# plotter.net
KiCad netlist of a schematic drawn in EAGLE
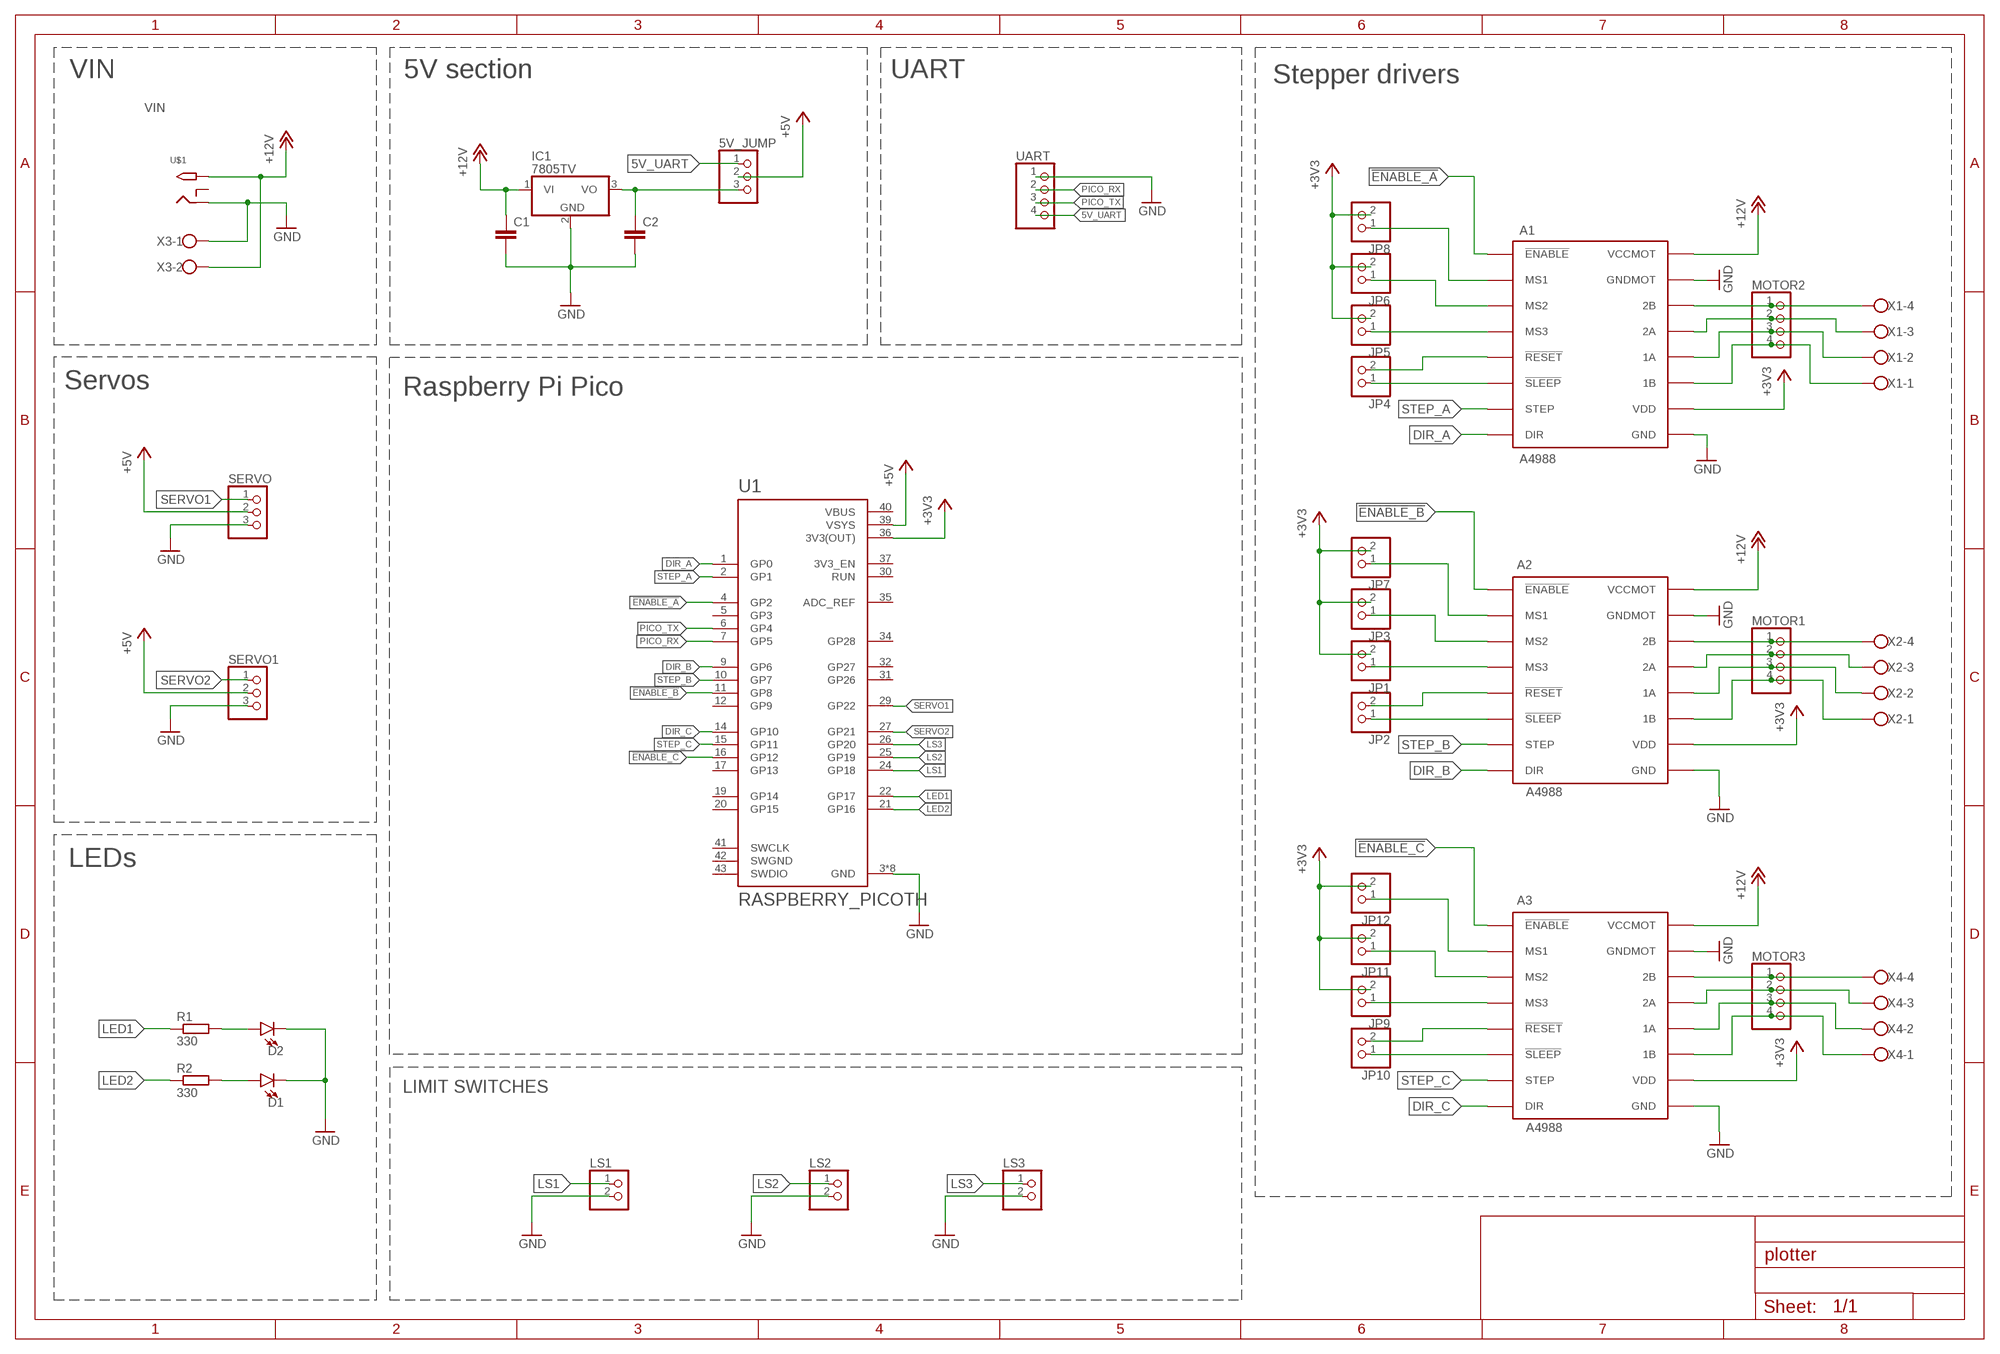
[diagram p0: schematic, sheet 1]

(export (version "E")
  (design (tool "Eeschema 10.0.6"))
  (components
    (comp (ref "5V_JUMP")
      (value "PINHD-1X3")
      (footprint "eagle-import:1X03")
      (libsource (lib "eagle-import") (part "PINHD-1X3"))
    )
    (comp (ref "A1")
      (value "A4988")
      (footprint "eagle-import:A4988")
      (libsource (lib "eagle-import") (part "A4988"))
    )
    (comp (ref "A2")
      (value "A4988")
      (footprint "eagle-import:A4988")
      (libsource (lib "eagle-import") (part "A4988"))
    )
    (comp (ref "A3")
      (value "A4988")
      (footprint "eagle-import:A4988")
      (libsource (lib "eagle-import") (part "A4988"))
    )
    (comp (ref "C1")
      (value "C-EUC0805")
      (footprint "eagle-import:C0805")
      (libsource (lib "eagle-import") (part "C-EUC0805"))
    )
    (comp (ref "C2")
      (value "C-EUC0805")
      (footprint "eagle-import:C0805")
      (libsource (lib "eagle-import") (part "C-EUC0805"))
    )
    (comp (ref "D1")
      (value "LED5MM")
      (footprint "eagle-import:LED_5MM")
      (libsource (lib "eagle-import") (part "LED5MM"))
    )
    (comp (ref "D2")
      (value "LED5MM")
      (footprint "eagle-import:LED_5MM")
      (libsource (lib "eagle-import") (part "LED5MM"))
    )
    (comp (ref "IC1")
      (value "7805TV")
      (footprint "eagle-import:TO220V")
      (libsource (lib "eagle-import") (part "78TV05"))
    )
    (comp (ref "JP1")
      (value "PINHD-1X2")
      (footprint "eagle-import:1X02")
      (libsource (lib "eagle-import") (part "PINHD-1X2"))
    )
    (comp (ref "JP2")
      (value "PINHD-1X2")
      (footprint "eagle-import:1X02")
      (libsource (lib "eagle-import") (part "PINHD-1X2"))
    )
    (comp (ref "JP3")
      (value "PINHD-1X2")
      (footprint "eagle-import:1X02")
      (libsource (lib "eagle-import") (part "PINHD-1X2"))
    )
    (comp (ref "JP4")
      (value "PINHD-1X2")
      (footprint "eagle-import:1X02")
      (libsource (lib "eagle-import") (part "PINHD-1X2"))
    )
    (comp (ref "JP5")
      (value "PINHD-1X2")
      (footprint "eagle-import:1X02")
      (libsource (lib "eagle-import") (part "PINHD-1X2"))
    )
    (comp (ref "JP6")
      (value "PINHD-1X2")
      (footprint "eagle-import:1X02")
      (libsource (lib "eagle-import") (part "PINHD-1X2"))
    )
    (comp (ref "JP7")
      (value "PINHD-1X2")
      (footprint "eagle-import:1X02")
      (libsource (lib "eagle-import") (part "PINHD-1X2"))
    )
    (comp (ref "JP8")
      (value "PINHD-1X2")
      (footprint "eagle-import:1X02")
      (libsource (lib "eagle-import") (part "PINHD-1X2"))
    )
    (comp (ref "JP9")
      (value "PINHD-1X2")
      (footprint "eagle-import:1X02")
      (libsource (lib "eagle-import") (part "PINHD-1X2"))
    )
    (comp (ref "JP10")
      (value "PINHD-1X2")
      (footprint "eagle-import:1X02")
      (libsource (lib "eagle-import") (part "PINHD-1X2"))
    )
    (comp (ref "JP11")
      (value "PINHD-1X2")
      (footprint "eagle-import:1X02")
      (libsource (lib "eagle-import") (part "PINHD-1X2"))
    )
    (comp (ref "JP12")
      (value "PINHD-1X2")
      (footprint "eagle-import:1X02")
      (libsource (lib "eagle-import") (part "PINHD-1X2"))
    )
    (comp (ref "LS1")
      (value "PINHD-1X2")
      (footprint "eagle-import:1X02")
      (libsource (lib "eagle-import") (part "PINHD-1X2"))
    )
    (comp (ref "LS2")
      (value "PINHD-1X2")
      (footprint "eagle-import:1X02")
      (libsource (lib "eagle-import") (part "PINHD-1X2"))
    )
    (comp (ref "LS3")
      (value "PINHD-1X2")
      (footprint "eagle-import:1X02")
      (libsource (lib "eagle-import") (part "PINHD-1X2"))
    )
    (comp (ref "MOTOR1")
      (value "PINHD-1X4")
      (footprint "eagle-import:1X04")
      (libsource (lib "eagle-import") (part "PINHD-1X4"))
    )
    (comp (ref "MOTOR2")
      (value "PINHD-1X4")
      (footprint "eagle-import:1X04")
      (libsource (lib "eagle-import") (part "PINHD-1X4"))
    )
    (comp (ref "MOTOR3")
      (value "PINHD-1X4")
      (footprint "eagle-import:1X04")
      (libsource (lib "eagle-import") (part "PINHD-1X4"))
    )
    (comp (ref "R1")
      (value "330")
      (footprint "eagle-import:R0805")
      (libsource (lib "eagle-import") (part "R-EU_R0805"))
    )
    (comp (ref "R2")
      (value "330")
      (footprint "eagle-import:R0805")
      (libsource (lib "eagle-import") (part "R-EU_R0805"))
    )
    (comp (ref "SERVO")
      (value "PINHD-1X3")
      (footprint "eagle-import:1X03")
      (libsource (lib "eagle-import") (part "PINHD-1X3"))
    )
    (comp (ref "SERVO1")
      (value "PINHD-1X3")
      (footprint "eagle-import:1X03")
      (libsource (lib "eagle-import") (part "PINHD-1X3"))
    )
    (comp (ref "U$1")
      (value "2.1MMJACKTHM")
      (footprint "eagle-import:PJ-102A")
      (libsource (lib "eagle-import") (part "2.1MMJACKTHM"))
    )
    (comp (ref "U1")
      (value "RASPBERRY_PICOTH")
      (footprint "eagle-import:PICO-PKG-TH")
      (libsource (lib "eagle-import") (part "RASPBERRY_PICOTH"))
    )
    (comp (ref "UART")
      (value "PINHD-1X4")
      (footprint "eagle-import:1X04")
      (libsource (lib "eagle-import") (part "PINHD-1X4"))
    )
    (comp (ref "X1")
      (value "W237-4")
      (footprint "eagle-import:W237-4")
      (libsource (lib "eagle-import") (part "W237-4"))
    )
    (comp (ref "X2")
      (value "W237-4")
      (footprint "eagle-import:W237-4")
      (libsource (lib "eagle-import") (part "W237-4"))
    )
    (comp (ref "X3")
      (value "W237-102")
      (footprint "eagle-import:W237-102")
      (fields (field (name "MPN") "237-102"))
      (libsource (lib "eagle-import") (part "W237-102"))
    )
    (comp (ref "X4")
      (value "W237-4")
      (footprint "eagle-import:W237-4")
      (libsource (lib "eagle-import") (part "W237-4"))
    )
  )
  (nets
    (net (code "1") (name "+3V3") (class "Default")
      (node (ref "A1") (pin "VDD") (pinfunction "VDD_VDD") (pintype "bidirectional"))
      (node (ref "A2") (pin "VDD") (pinfunction "VDD_VDD") (pintype "bidirectional"))
      (node (ref "A3") (pin "VDD") (pinfunction "VDD_VDD") (pintype "bidirectional"))
      (node (ref "JP1") (pin "2") (pinfunction "2_2") (pintype "passive"))
      (node (ref "JP11") (pin "2") (pinfunction "2_2") (pintype "passive"))
      (node (ref "JP12") (pin "2") (pinfunction "2_2") (pintype "passive"))
      (node (ref "JP3") (pin "2") (pinfunction "2_2") (pintype "passive"))
      (node (ref "JP5") (pin "2") (pinfunction "2_2") (pintype "passive"))
      (node (ref "JP6") (pin "2") (pinfunction "2_2") (pintype "passive"))
      (node (ref "JP7") (pin "2") (pinfunction "2_2") (pintype "passive"))
      (node (ref "JP8") (pin "2") (pinfunction "2_2") (pintype "passive"))
      (node (ref "JP9") (pin "2") (pinfunction "2_2") (pintype "passive"))
      (node (ref "U1") (pin "36") (pinfunction "3V3(OUT)_36") (pintype "power_in"))
    )
    (net (code "2") (name "+5V") (class "Default")
      (node (ref "5V_JUMP") (pin "2") (pinfunction "2_2") (pintype "passive"))
      (node (ref "SERVO") (pin "2") (pinfunction "2_2") (pintype "passive"))
      (node (ref "SERVO1") (pin "2") (pinfunction "2_2") (pintype "passive"))
      (node (ref "U1") (pin "39") (pinfunction "VSYS_39") (pintype "power_in"))
    )
    (net (code "3") (name "+12V") (class "Default")
      (node (ref "A1") (pin "VCCMOT") (pinfunction "VCCMOT_VCCMOT") (pintype "bidirectional"))
      (node (ref "A2") (pin "VCCMOT") (pinfunction "VCCMOT_VCCMOT") (pintype "bidirectional"))
      (node (ref "A3") (pin "VCCMOT") (pinfunction "VCCMOT_VCCMOT") (pintype "bidirectional"))
      (node (ref "C1") (pin "1") (pinfunction "1_1") (pintype "passive"))
      (node (ref "IC1") (pin "1") (pinfunction "VI_1") (pintype "input"))
      (node (ref "U$1") (pin "TIP") (pinfunction "TIP_TIP") (pintype "bidirectional"))
      (node (ref "X3") (pin "2") (pinfunction "KL_2") (pintype "passive"))
    )
    (net (code "4") (name "/SWGND") (class "Default")
      (node (ref "U1") (pin "42") (pinfunction "SWGND_42") (pintype "power_in"))
    )
    (net (code "5") (name "/VBUS") (class "Default")
      (node (ref "U1") (pin "40") (pinfunction "VBUS_40") (pintype "power_in"))
    )
    (net (code "6") (name "/~{ENABLE_A}") (class "Default")
      (node (ref "A1") (pin "!ENABLE") (pinfunction "~{ENABLE}_!ENABLE") (pintype "bidirectional"))
      (node (ref "U1") (pin "4") (pinfunction "GP2_4") (pintype "bidirectional"))
    )
    (net (code "7") (name "/~{ENABLE_B}") (class "Default")
      (node (ref "A2") (pin "!ENABLE") (pinfunction "~{ENABLE}_!ENABLE") (pintype "bidirectional"))
      (node (ref "U1") (pin "11") (pinfunction "GP8_11") (pintype "bidirectional"))
    )
    (net (code "8") (name "/~{ENABLE_C}") (class "Default")
      (node (ref "A3") (pin "!ENABLE") (pinfunction "~{ENABLE}_!ENABLE") (pintype "bidirectional"))
      (node (ref "U1") (pin "16") (pinfunction "GP12_16") (pintype "bidirectional"))
    )
    (net (code "9") (name "5V_UART") (class "Default")
      (node (ref "5V_JUMP") (pin "1") (pinfunction "1_1") (pintype "passive"))
      (node (ref "UART") (pin "4") (pinfunction "4_4") (pintype "passive"))
    )
    (net (code "10") (name "DIR_A") (class "Default")
      (node (ref "A1") (pin "DIR") (pinfunction "DIR_DIR") (pintype "bidirectional"))
      (node (ref "U1") (pin "1") (pinfunction "GP0_1") (pintype "bidirectional"))
    )
    (net (code "11") (name "DIR_B") (class "Default")
      (node (ref "A2") (pin "DIR") (pinfunction "DIR_DIR") (pintype "bidirectional"))
      (node (ref "U1") (pin "9") (pinfunction "GP6_9") (pintype "bidirectional"))
    )
    (net (code "12") (name "DIR_C") (class "Default")
      (node (ref "A3") (pin "DIR") (pinfunction "DIR_DIR") (pintype "bidirectional"))
      (node (ref "U1") (pin "14") (pinfunction "GP10_14") (pintype "bidirectional"))
    )
    (net (code "13") (name "GND") (class "Default")
      (node (ref "A1") (pin "GND") (pinfunction "GND_GND") (pintype "bidirectional"))
      (node (ref "A1") (pin "GNDMOT") (pinfunction "GNDMOT_GNDMOT") (pintype "bidirectional"))
      (node (ref "A2") (pin "GND") (pinfunction "GND_GND") (pintype "bidirectional"))
      (node (ref "A2") (pin "GNDMOT") (pinfunction "GNDMOT_GNDMOT") (pintype "bidirectional"))
      (node (ref "A3") (pin "GND") (pinfunction "GND_GND") (pintype "bidirectional"))
      (node (ref "A3") (pin "GNDMOT") (pinfunction "GNDMOT_GNDMOT") (pintype "bidirectional"))
      (node (ref "C1") (pin "2") (pinfunction "2_2") (pintype "passive"))
      (node (ref "C2") (pin "2") (pinfunction "2_2") (pintype "passive"))
      (node (ref "D1") (pin "K") (pinfunction "C_K") (pintype "passive"))
      (node (ref "D2") (pin "K") (pinfunction "C_K") (pintype "passive"))
      (node (ref "IC1") (pin "2") (pinfunction "GND_2") (pintype "passive"))
      (node (ref "LS1") (pin "2") (pinfunction "2_2") (pintype "passive"))
      (node (ref "LS2") (pin "2") (pinfunction "2_2") (pintype "passive"))
      (node (ref "LS3") (pin "2") (pinfunction "2_2") (pintype "passive"))
      (node (ref "SERVO") (pin "3") (pinfunction "3_3") (pintype "passive"))
      (node (ref "SERVO1") (pin "3") (pinfunction "3_3") (pintype "passive"))
      (node (ref "U$1") (pin "RING") (pinfunction "RING_RING") (pintype "bidirectional"))
      (node (ref "U1") (pin "13") (pinfunction "GND_13") (pintype "power_in"))
      (node (ref "U1") (pin "18") (pinfunction "GND_18") (pintype "power_in"))
      (node (ref "U1") (pin "23") (pinfunction "GND_23") (pintype "power_in"))
      (node (ref "U1") (pin "28") (pinfunction "GND_28") (pintype "power_in"))
      (node (ref "U1") (pin "3") (pinfunction "GND_3") (pintype "power_in"))
      (node (ref "U1") (pin "33") (pinfunction "GND_33") (pintype "power_in"))
      (node (ref "U1") (pin "38") (pinfunction "GND_38") (pintype "power_in"))
      (node (ref "U1") (pin "8") (pinfunction "GND_8") (pintype "power_in"))
      (node (ref "UART") (pin "1") (pinfunction "1_1") (pintype "passive"))
      (node (ref "X3") (pin "1") (pinfunction "KL_1") (pintype "passive"))
    )
    (net (code "14") (name "LED1") (class "Default")
      (node (ref "R1") (pin "1") (pinfunction "1_1") (pintype "passive"))
      (node (ref "U1") (pin "22") (pinfunction "GP17_22") (pintype "bidirectional"))
    )
    (net (code "15") (name "LED2") (class "Default")
      (node (ref "R2") (pin "1") (pinfunction "1_1") (pintype "passive"))
      (node (ref "U1") (pin "21") (pinfunction "GP16_21") (pintype "bidirectional"))
    )
    (net (code "16") (name "LS1") (class "Default")
      (node (ref "LS1") (pin "1") (pinfunction "1_1") (pintype "passive"))
      (node (ref "U1") (pin "24") (pinfunction "GP18_24") (pintype "bidirectional"))
    )
    (net (code "17") (name "LS2") (class "Default")
      (node (ref "LS2") (pin "1") (pinfunction "1_1") (pintype "passive"))
      (node (ref "U1") (pin "25") (pinfunction "GP19_25") (pintype "bidirectional"))
    )
    (net (code "18") (name "LS3") (class "Default")
      (node (ref "LS3") (pin "1") (pinfunction "1_1") (pintype "passive"))
      (node (ref "U1") (pin "26") (pinfunction "GP20_26") (pintype "bidirectional"))
    )
    (net (code "19") (name "Net-(A1-PadMS1)") (class "Default")
      (node (ref "A1") (pin "MS1") (pinfunction "MS1_MS1") (pintype "bidirectional"))
      (node (ref "JP8") (pin "1") (pinfunction "1_1") (pintype "passive"))
    )
    (net (code "20") (name "Net-(A1-PadMS2)") (class "Default")
      (node (ref "A1") (pin "MS2") (pinfunction "MS2_MS2") (pintype "bidirectional"))
      (node (ref "JP6") (pin "1") (pinfunction "1_1") (pintype "passive"))
    )
    (net (code "21") (name "Net-(A1-PadMS3)") (class "Default")
      (node (ref "A1") (pin "MS3") (pinfunction "MS3_MS3") (pintype "bidirectional"))
      (node (ref "JP5") (pin "1") (pinfunction "1_1") (pintype "passive"))
    )
    (net (code "22") (name "Net-(A1-~{RESET})") (class "Default")
      (node (ref "A1") (pin "!RESET") (pinfunction "~{RESET}_!RESET") (pintype "bidirectional"))
      (node (ref "JP4") (pin "2") (pinfunction "2_2") (pintype "passive"))
    )
    (net (code "23") (name "Net-(A1-~{SLEEP})") (class "Default")
      (node (ref "A1") (pin "!SLEEP") (pinfunction "~{SLEEP}_!SLEEP") (pintype "bidirectional"))
      (node (ref "JP4") (pin "1") (pinfunction "1_1") (pintype "passive"))
    )
    (net (code "24") (name "Net-(A2-PadMS1)") (class "Default")
      (node (ref "A2") (pin "MS1") (pinfunction "MS1_MS1") (pintype "bidirectional"))
      (node (ref "JP7") (pin "1") (pinfunction "1_1") (pintype "passive"))
    )
    (net (code "25") (name "Net-(A2-PadMS2)") (class "Default")
      (node (ref "A2") (pin "MS2") (pinfunction "MS2_MS2") (pintype "bidirectional"))
      (node (ref "JP3") (pin "1") (pinfunction "1_1") (pintype "passive"))
    )
    (net (code "26") (name "Net-(A2-PadMS3)") (class "Default")
      (node (ref "A2") (pin "MS3") (pinfunction "MS3_MS3") (pintype "bidirectional"))
      (node (ref "JP1") (pin "1") (pinfunction "1_1") (pintype "passive"))
    )
    (net (code "27") (name "Net-(A2-~{RESET})") (class "Default")
      (node (ref "A2") (pin "!RESET") (pinfunction "~{RESET}_!RESET") (pintype "bidirectional"))
      (node (ref "JP2") (pin "2") (pinfunction "2_2") (pintype "passive"))
    )
    (net (code "28") (name "Net-(A2-~{SLEEP})") (class "Default")
      (node (ref "A2") (pin "!SLEEP") (pinfunction "~{SLEEP}_!SLEEP") (pintype "bidirectional"))
      (node (ref "JP2") (pin "1") (pinfunction "1_1") (pintype "passive"))
    )
    (net (code "29") (name "Net-(A3-PadMS1)") (class "Default")
      (node (ref "A3") (pin "MS1") (pinfunction "MS1_MS1") (pintype "bidirectional"))
      (node (ref "JP12") (pin "1") (pinfunction "1_1") (pintype "passive"))
    )
    (net (code "30") (name "Net-(A3-PadMS2)") (class "Default")
      (node (ref "A3") (pin "MS2") (pinfunction "MS2_MS2") (pintype "bidirectional"))
      (node (ref "JP11") (pin "1") (pinfunction "1_1") (pintype "passive"))
    )
    (net (code "31") (name "Net-(A3-PadMS3)") (class "Default")
      (node (ref "A3") (pin "MS3") (pinfunction "MS3_MS3") (pintype "bidirectional"))
      (node (ref "JP9") (pin "1") (pinfunction "1_1") (pintype "passive"))
    )
    (net (code "32") (name "Net-(A3-~{RESET})") (class "Default")
      (node (ref "A3") (pin "!RESET") (pinfunction "~{RESET}_!RESET") (pintype "bidirectional"))
      (node (ref "JP10") (pin "2") (pinfunction "2_2") (pintype "passive"))
    )
    (net (code "33") (name "Net-(A3-~{SLEEP})") (class "Default")
      (node (ref "A3") (pin "!SLEEP") (pinfunction "~{SLEEP}_!SLEEP") (pintype "bidirectional"))
      (node (ref "JP10") (pin "1") (pinfunction "1_1") (pintype "passive"))
    )
    (net (code "34") (name "Net-(D1-PadA)") (class "Default")
      (node (ref "D1") (pin "A") (pinfunction "A_A") (pintype "passive"))
      (node (ref "R2") (pin "2") (pinfunction "2_2") (pintype "passive"))
    )
    (net (code "35") (name "Net-(D2-PadA)") (class "Default")
      (node (ref "D2") (pin "A") (pinfunction "A_A") (pintype "passive"))
      (node (ref "R1") (pin "2") (pinfunction "2_2") (pintype "passive"))
    )
    (net (code "36") (name "Net-(IC1-VO)") (class "Default")
      (node (ref "5V_JUMP") (pin "3") (pinfunction "3_3") (pintype "passive"))
      (node (ref "C2") (pin "1") (pinfunction "1_1") (pintype "passive"))
      (node (ref "IC1") (pin "3") (pinfunction "VO_3") (pintype "passive"))
    )
    (net (code "37") (name "Net-(X1A-KL)") (class "Default")
      (node (ref "A1") (pin "1B") (pinfunction "1B_1B") (pintype "bidirectional"))
      (node (ref "MOTOR2") (pin "4") (pinfunction "4_4") (pintype "passive"))
      (node (ref "X1") (pin "1") (pinfunction "KL_1") (pintype "passive"))
    )
    (net (code "38") (name "Net-(X1B-KL)") (class "Default")
      (node (ref "A1") (pin "1A") (pinfunction "1A_1A") (pintype "bidirectional"))
      (node (ref "MOTOR2") (pin "3") (pinfunction "3_3") (pintype "passive"))
      (node (ref "X1") (pin "2") (pinfunction "KL_2") (pintype "passive"))
    )
    (net (code "39") (name "Net-(X1C-KL)") (class "Default")
      (node (ref "A1") (pin "2A") (pinfunction "2A_2A") (pintype "bidirectional"))
      (node (ref "MOTOR2") (pin "2") (pinfunction "2_2") (pintype "passive"))
      (node (ref "X1") (pin "3") (pinfunction "KL_3") (pintype "passive"))
    )
    (net (code "40") (name "Net-(X1D-KL)") (class "Default")
      (node (ref "A1") (pin "2B") (pinfunction "2B_2B") (pintype "bidirectional"))
      (node (ref "MOTOR2") (pin "1") (pinfunction "1_1") (pintype "passive"))
      (node (ref "X1") (pin "4") (pinfunction "KL_4") (pintype "passive"))
    )
    (net (code "41") (name "Net-(X2A-KL)") (class "Default")
      (node (ref "A2") (pin "1B") (pinfunction "1B_1B") (pintype "bidirectional"))
      (node (ref "MOTOR1") (pin "4") (pinfunction "4_4") (pintype "passive"))
      (node (ref "X2") (pin "1") (pinfunction "KL_1") (pintype "passive"))
    )
    (net (code "42") (name "Net-(X2B-KL)") (class "Default")
      (node (ref "A2") (pin "1A") (pinfunction "1A_1A") (pintype "bidirectional"))
      (node (ref "MOTOR1") (pin "3") (pinfunction "3_3") (pintype "passive"))
      (node (ref "X2") (pin "2") (pinfunction "KL_2") (pintype "passive"))
    )
    (net (code "43") (name "Net-(X2C-KL)") (class "Default")
      (node (ref "A2") (pin "2A") (pinfunction "2A_2A") (pintype "bidirectional"))
      (node (ref "MOTOR1") (pin "2") (pinfunction "2_2") (pintype "passive"))
      (node (ref "X2") (pin "3") (pinfunction "KL_3") (pintype "passive"))
    )
    (net (code "44") (name "Net-(X2D-KL)") (class "Default")
      (node (ref "A2") (pin "2B") (pinfunction "2B_2B") (pintype "bidirectional"))
      (node (ref "MOTOR1") (pin "1") (pinfunction "1_1") (pintype "passive"))
      (node (ref "X2") (pin "4") (pinfunction "KL_4") (pintype "passive"))
    )
    (net (code "45") (name "Net-(X4A-KL)") (class "Default")
      (node (ref "A3") (pin "1B") (pinfunction "1B_1B") (pintype "bidirectional"))
      (node (ref "MOTOR3") (pin "4") (pinfunction "4_4") (pintype "passive"))
      (node (ref "X4") (pin "1") (pinfunction "KL_1") (pintype "passive"))
    )
    (net (code "46") (name "Net-(X4B-KL)") (class "Default")
      (node (ref "A3") (pin "1A") (pinfunction "1A_1A") (pintype "bidirectional"))
      (node (ref "MOTOR3") (pin "3") (pinfunction "3_3") (pintype "passive"))
      (node (ref "X4") (pin "2") (pinfunction "KL_2") (pintype "passive"))
    )
    (net (code "47") (name "Net-(X4C-KL)") (class "Default")
      (node (ref "A3") (pin "2A") (pinfunction "2A_2A") (pintype "bidirectional"))
      (node (ref "MOTOR3") (pin "2") (pinfunction "2_2") (pintype "passive"))
      (node (ref "X4") (pin "3") (pinfunction "KL_3") (pintype "passive"))
    )
    (net (code "48") (name "Net-(X4D-KL)") (class "Default")
      (node (ref "A3") (pin "2B") (pinfunction "2B_2B") (pintype "bidirectional"))
      (node (ref "MOTOR3") (pin "1") (pinfunction "1_1") (pintype "passive"))
      (node (ref "X4") (pin "4") (pinfunction "KL_4") (pintype "passive"))
    )
    (net (code "49") (name "PICO_RX") (class "Default")
      (node (ref "U1") (pin "7") (pinfunction "GP5_7") (pintype "bidirectional"))
      (node (ref "UART") (pin "2") (pinfunction "2_2") (pintype "passive"))
    )
    (net (code "50") (name "PICO_TX") (class "Default")
      (node (ref "U1") (pin "6") (pinfunction "GP4_6") (pintype "bidirectional"))
      (node (ref "UART") (pin "3") (pinfunction "3_3") (pintype "passive"))
    )
    (net (code "51") (name "SERVO1") (class "Default")
      (node (ref "SERVO") (pin "1") (pinfunction "1_1") (pintype "passive"))
      (node (ref "U1") (pin "29") (pinfunction "GP22_29") (pintype "bidirectional"))
    )
    (net (code "52") (name "SERVO2") (class "Default")
      (node (ref "SERVO1") (pin "1") (pinfunction "1_1") (pintype "passive"))
      (node (ref "U1") (pin "27") (pinfunction "GP21_27") (pintype "bidirectional"))
    )
    (net (code "53") (name "STEP_A") (class "Default")
      (node (ref "A1") (pin "STEP") (pinfunction "STEP_STEP") (pintype "bidirectional"))
      (node (ref "U1") (pin "2") (pinfunction "GP1_2") (pintype "bidirectional"))
    )
    (net (code "54") (name "STEP_B") (class "Default")
      (node (ref "A2") (pin "STEP") (pinfunction "STEP_STEP") (pintype "bidirectional"))
      (node (ref "U1") (pin "10") (pinfunction "GP7_10") (pintype "bidirectional"))
    )
    (net (code "55") (name "STEP_C") (class "Default")
      (node (ref "A3") (pin "STEP") (pinfunction "STEP_STEP") (pintype "bidirectional"))
      (node (ref "U1") (pin "15") (pinfunction "GP11_15") (pintype "bidirectional"))
    )
    (net (code "56") (name "unconnected-(U$1-PadRING_SW)") (class "Default")
      (node (ref "U$1") (pin "RING_SW") (pinfunction "RING_SW_RING_SW") (pintype "bidirectional"))
    )
    (net (code "57") (name "unconnected-(U1-3V3_EN-Pad37)") (class "Default")
      (node (ref "U1") (pin "37") (pinfunction "3V3_EN_37") (pintype "input"))
    )
    (net (code "58") (name "unconnected-(U1-ADC_REF-Pad35)") (class "Default")
      (node (ref "U1") (pin "35") (pinfunction "ADC_REF_35") (pintype "input"))
    )
    (net (code "59") (name "unconnected-(U1-GP3-Pad5)") (class "Default")
      (node (ref "U1") (pin "5") (pinfunction "GP3_5") (pintype "bidirectional"))
    )
    (net (code "60") (name "unconnected-(U1-GP9-Pad12)") (class "Default")
      (node (ref "U1") (pin "12") (pinfunction "GP9_12") (pintype "bidirectional"))
    )
    (net (code "61") (name "unconnected-(U1-GP13-Pad17)") (class "Default")
      (node (ref "U1") (pin "17") (pinfunction "GP13_17") (pintype "bidirectional"))
    )
    (net (code "62") (name "unconnected-(U1-GP14-Pad19)") (class "Default")
      (node (ref "U1") (pin "19") (pinfunction "GP14_19") (pintype "bidirectional"))
    )
    (net (code "63") (name "unconnected-(U1-GP15-Pad20)") (class "Default")
      (node (ref "U1") (pin "20") (pinfunction "GP15_20") (pintype "bidirectional"))
    )
    (net (code "64") (name "unconnected-(U1-GP26-Pad31)") (class "Default")
      (node (ref "U1") (pin "31") (pinfunction "GP26_31") (pintype "bidirectional"))
    )
    (net (code "65") (name "unconnected-(U1-GP27-Pad32)") (class "Default")
      (node (ref "U1") (pin "32") (pinfunction "GP27_32") (pintype "bidirectional"))
    )
    (net (code "66") (name "unconnected-(U1-GP28-Pad34)") (class "Default")
      (node (ref "U1") (pin "34") (pinfunction "GP28_34") (pintype "bidirectional"))
    )
    (net (code "67") (name "unconnected-(U1-RUN-Pad30)") (class "Default")
      (node (ref "U1") (pin "30") (pinfunction "RUN_30") (pintype "input"))
    )
    (net (code "68") (name "unconnected-(U1-SWCLK-Pad41)") (class "Default")
      (node (ref "U1") (pin "41") (pinfunction "SWCLK_41") (pintype "input"))
    )
    (net (code "69") (name "unconnected-(U1-SWDIO-Pad43)") (class "Default")
      (node (ref "U1") (pin "43") (pinfunction "SWDIO_43") (pintype "bidirectional"))
    )
  )
)
